# MCU_Do_An_2.net
KiCad netlist of a schematic drawn in Altium Designer
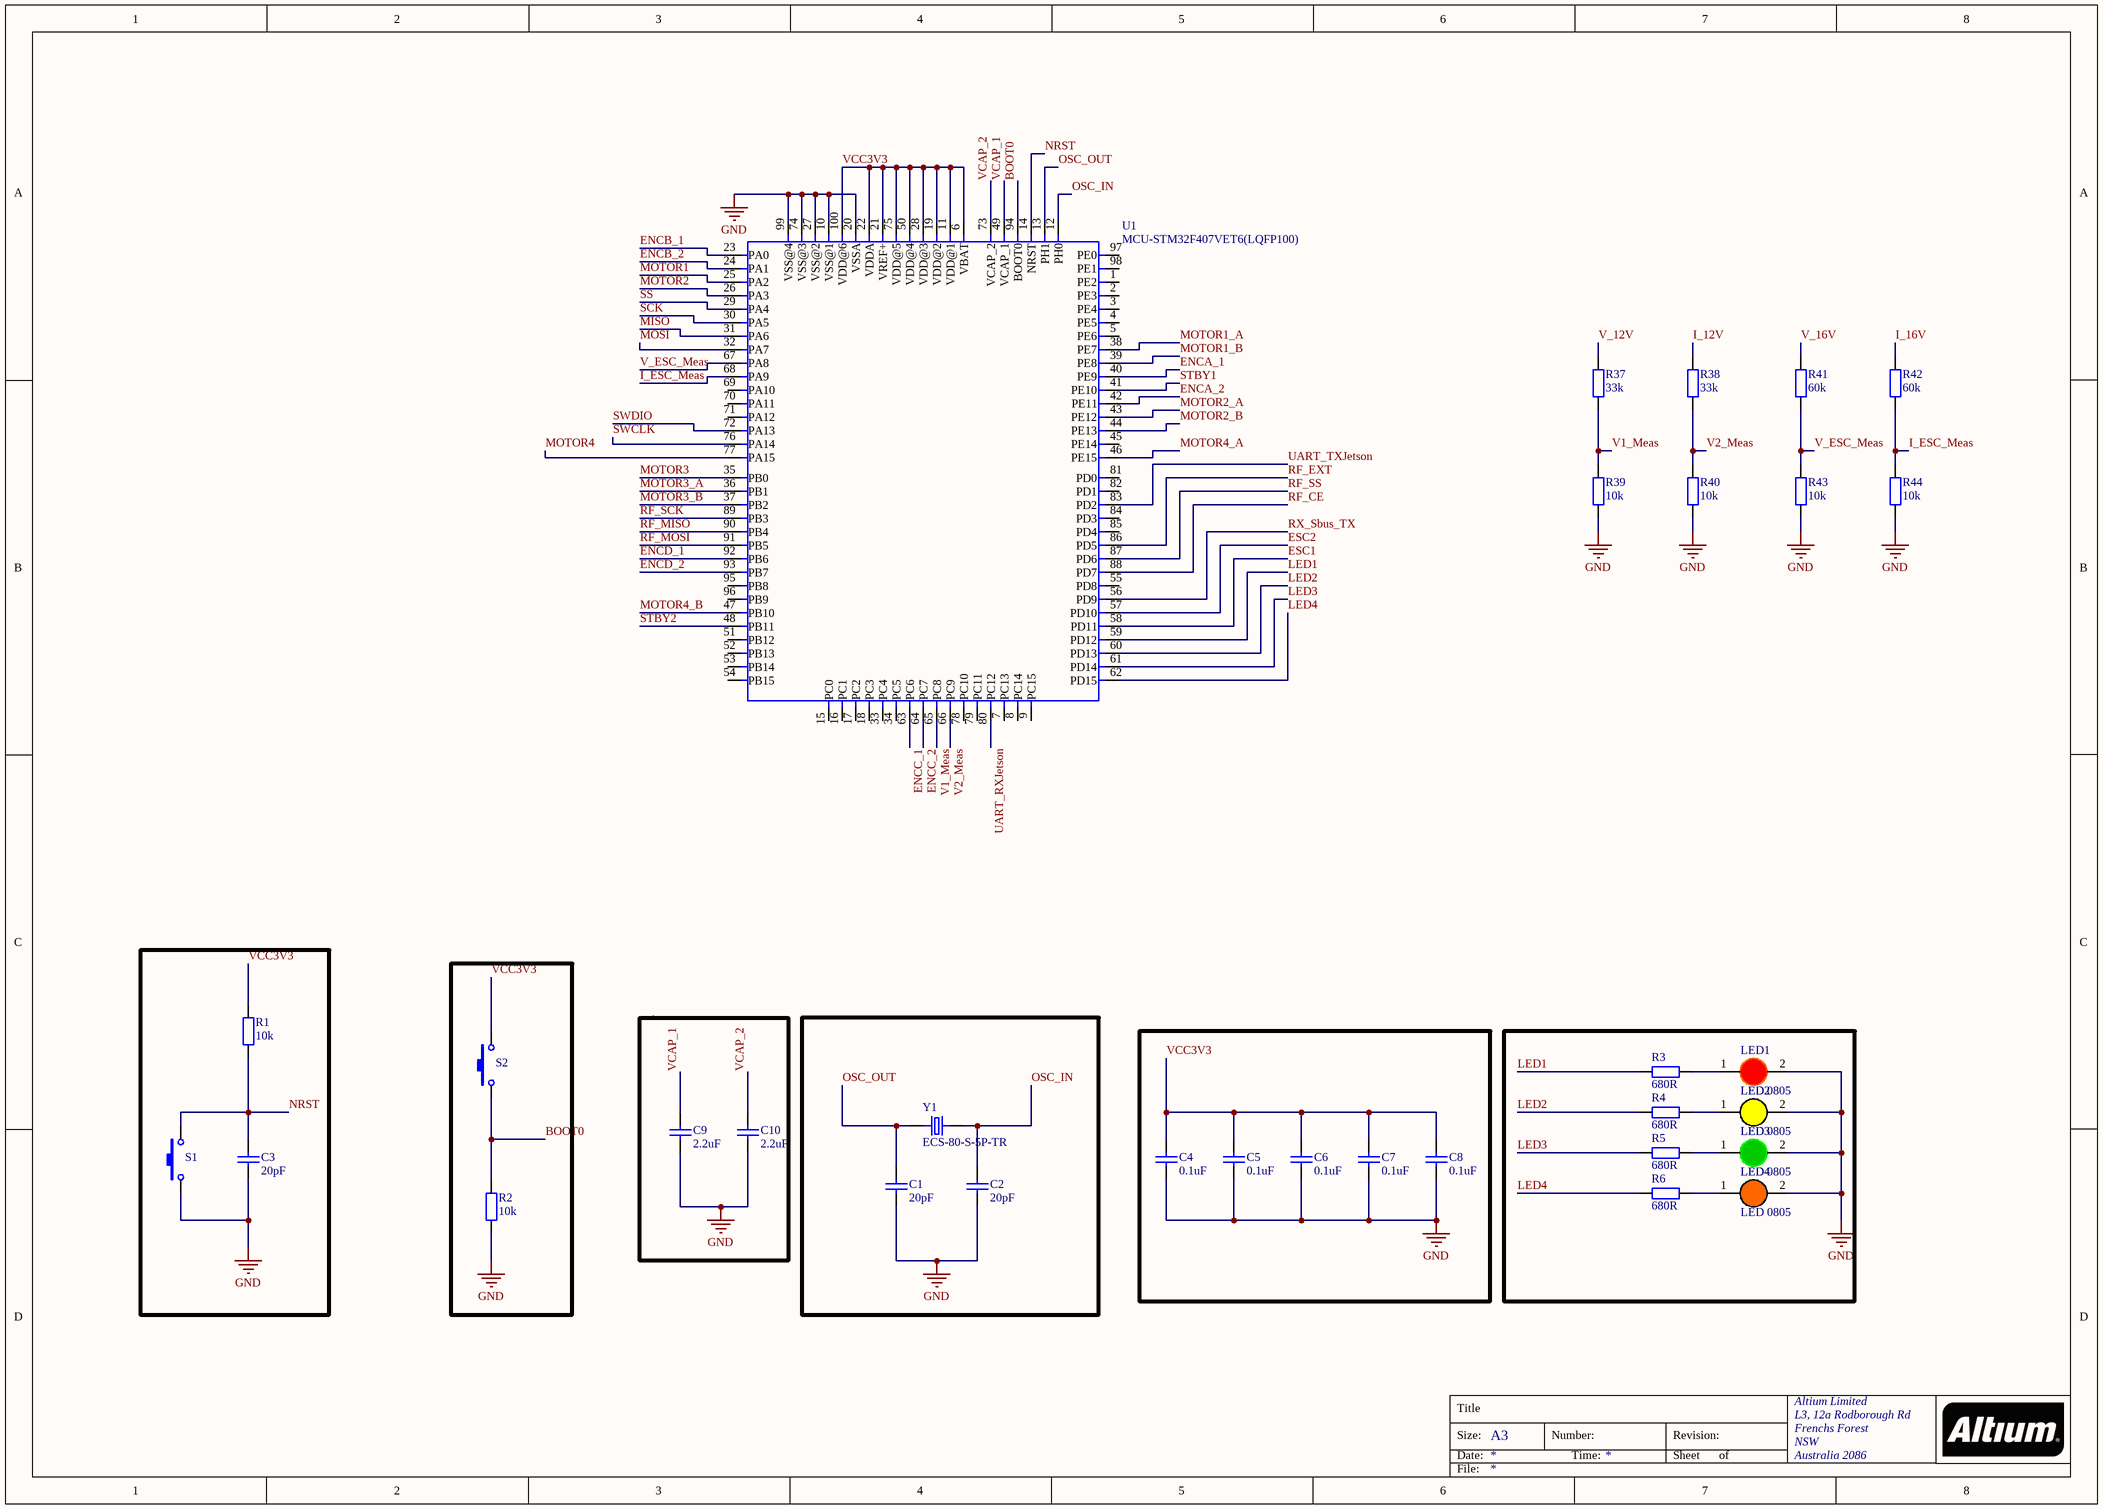
[diagram p0: MCU_Do_An_2.SchDoc]

(export (version "E")
  (design (tool "Eeschema 10.0.6"))
  (components
    (comp (ref "C1")
      (value "20pF")
      (footprint "tu 0805")
      (description "Dán")
      (libsource (lib "Tu dien") (part "Tu 0805 20pF 50V 10%"))
    )
    (comp (ref "C2")
      (value "20pF")
      (footprint "tu 0805")
      (description "Dán")
      (libsource (lib "Tu dien") (part "Tu 0805 20pF 50V 10%"))
    )
    (comp (ref "C3")
      (value "20pF")
      (footprint "tu 0805")
      (description "Dán")
      (libsource (lib "Tu dien") (part "Tu 0805 20pF 50V 10%"))
    )
    (comp (ref "C4")
      (value "0.1uF")
      (footprint "tu 0805")
      (description "Dán")
      (libsource (lib "Tu dien") (part "Tu 0805 20pF 50V 10%"))
    )
    (comp (ref "C5")
      (value "0.1uF")
      (footprint "tu 0805")
      (description "Dán")
      (libsource (lib "Tu dien") (part "Tu 0805 20pF 50V 10%"))
    )
    (comp (ref "C6")
      (value "0.1uF")
      (footprint "tu 0805")
      (description "Dán")
      (libsource (lib "Tu dien") (part "Tu 0805 20pF 50V 10%"))
    )
    (comp (ref "C7")
      (value "0.1uF")
      (footprint "tu 0805")
      (description "Dán")
      (libsource (lib "Tu dien") (part "Tu 0805 20pF 50V 10%"))
    )
    (comp (ref "C8")
      (value "0.1uF")
      (footprint "tu 0805")
      (description "Dán")
      (libsource (lib "Tu dien") (part "Tu 0805 20pF 50V 10%"))
    )
    (comp (ref "C9")
      (value "2.2uF")
      (footprint "tu 0805")
      (description "Dán")
      (libsource (lib "Tu dien") (part "Tu 0805 225 25V 10%"))
    )
    (comp (ref "C10")
      (value "2.2uF")
      (footprint "tu 0805")
      (description "Dán")
      (libsource (lib "Tu dien") (part "Tu 0805 225 25V 10%"))
    )
    (comp (ref "LED1")
      (value "LED 0805")
      (footprint "LED-0805-Red")
      (description "Dán")
      (libsource (lib "Led") (part "LED 0805 Do"))
    )
    (comp (ref "LED2")
      (value "LED 0805")
      (footprint "LED-0805-Yellow")
      (description "Dán")
      (libsource (lib "Led") (part "LED 0805 Vang"))
    )
    (comp (ref "LED3")
      (value "LED 0805")
      (footprint "LED-0805-Green")
      (description "Dán")
      (libsource (lib "Led") (part "LED 0805 Xanh La"))
    )
    (comp (ref "LED4")
      (value "LED 0805")
      (footprint "LED-0805-Orange")
      (description "Dán")
      (libsource (lib "Led") (part "LED 0805 Cam"))
    )
    (comp (ref "R1")
      (value "10k")
      (footprint "tro smd 0603")
      (description "Dán")
      (libsource (lib "Dien Tro") (part "Tro 0603 1% 10k"))
    )
    (comp (ref "R2")
      (value "10k")
      (footprint "tro smd 0603")
      (description "Dán")
      (libsource (lib "Dien Tro") (part "Tro 0603 1% 10k"))
    )
    (comp (ref "R3")
      (value "680R")
      (footprint "tro smd 0603")
      (description "Dán")
      (libsource (lib "Dien Tro") (part "Tro 0603 1% 680R"))
    )
    (comp (ref "R4")
      (value "680R")
      (footprint "tro smd 0603")
      (description "Dán")
      (libsource (lib "Dien Tro") (part "Tro 0603 1% 680R"))
    )
    (comp (ref "R5")
      (value "680R")
      (footprint "tro smd 0603")
      (description "Dán")
      (libsource (lib "Dien Tro") (part "Tro 0603 1% 680R"))
    )
    (comp (ref "R6")
      (value "680R")
      (footprint "tro smd 0603")
      (description "Dán")
      (libsource (lib "Dien Tro") (part "Tro 0603 1% 680R"))
    )
    (comp (ref "R37")
      (value "33k")
      (footprint "Tro smd 0603")
      (description "Dán")
      (libsource (lib "Dien Tro") (part "Tro 0603 1% 33k"))
    )
    (comp (ref "R38")
      (value "33k")
      (footprint "Tro smd 0603")
      (description "Dán")
      (libsource (lib "Dien Tro") (part "Tro 0603 1% 33k"))
    )
    (comp (ref "R39")
      (value "10k")
      (footprint "tro smd 0603")
      (description "Dán")
      (libsource (lib "Dien Tro") (part "Tro 0603 1% 10k"))
    )
    (comp (ref "R40")
      (value "10k")
      (footprint "tro smd 0603")
      (description "Dán")
      (libsource (lib "Dien Tro") (part "Tro 0603 1% 10k"))
    )
    (comp (ref "R41")
      (value "60k")
      (footprint "Tro smd 0603")
      (description "Dán")
      (libsource (lib "Dien Tro") (part "Tro 0603 1% 33k"))
    )
    (comp (ref "R42")
      (value "60k")
      (footprint "Tro smd 0603")
      (description "Dán")
      (libsource (lib "Dien Tro") (part "Tro 0603 1% 33k"))
    )
    (comp (ref "R43")
      (value "10k")
      (footprint "tro smd 0603")
      (description "Dán")
      (libsource (lib "Dien Tro") (part "Tro 0603 1% 10k"))
    )
    (comp (ref "R44")
      (value "10k")
      (footprint "tro smd 0603")
      (description "Dán")
      (libsource (lib "Dien Tro") (part "Tro 0603 1% 10k"))
    )
    (comp (ref "S1")
      (value "SW-SMD")
      (footprint "SW-SMD")
      (description "Switch")
      (fields (field (name "PUBLISHER") "Altium Limited"))
      (libsource (lib "NBBLib 14-03-2012") (part "SW-SMD"))
    )
    (comp (ref "S2")
      (value "SW-SMD")
      (footprint "SW-SMD")
      (description "Switch")
      (fields (field (name "PUBLISHER") "Altium Limited"))
      (libsource (lib "NBBLib 14-03-2012") (part "SW-SMD"))
    )
    (comp (ref "U1")
      (value "MCU-STM32F407VET6(LQFP100)")
      (footprint "LQFP100-0.5-13.8X13.8MM")
      (fields (field (name "MP") "STM32F407VET6") (field (name "MF") "STMicroelectronics"))
      (libsource (lib "MCU-STM32F407VET6_LQFP100_") (part "MCU-STM32F407VET6(LQFP100)"))
    )
    (comp (ref "Y1")
      (value "ECS-80-S-5P-TR")
      (footprint "XTAL_ECS-80-S-5P-TR")
      (description "CRYSTAL SMD")
      (libsource (lib "ECS-80-S-5P-TR") (part "ECS-80-S-5P-TR"))
    )
  )
  (nets
    (net (code "1") (name "/BOOT0") (class "Default")
      (node (ref "R2") (pin "2") (pinfunction "2_2") (pintype "passive"))
      (node (ref "S2") (pin "1") (pinfunction "1_1") (pintype "passive"))
      (node (ref "U1") (pin "94") (pinfunction "BOOT0_94") (pintype "bidirectional"))
    )
    (net (code "2") (name "/ENCA_1") (class "Default")
      (node (ref "U1") (pin "40") (pinfunction "PE9_40") (pintype "bidirectional"))
    )
    (net (code "3") (name "/ENCA_2") (class "Default")
      (node (ref "U1") (pin "42") (pinfunction "PE11_42") (pintype "bidirectional"))
    )
    (net (code "4") (name "/ENCB_1") (class "Default")
      (node (ref "U1") (pin "23") (pinfunction "PA0_23") (pintype "bidirectional"))
    )
    (net (code "5") (name "/ENCB_2") (class "Default")
      (node (ref "U1") (pin "24") (pinfunction "PA1_24") (pintype "bidirectional"))
    )
    (net (code "6") (name "/ENCC_1") (class "Default")
      (node (ref "U1") (pin "63") (pinfunction "PC6_63") (pintype "bidirectional"))
    )
    (net (code "7") (name "/ENCC_2") (class "Default")
      (node (ref "U1") (pin "64") (pinfunction "PC7_64") (pintype "bidirectional"))
    )
    (net (code "8") (name "/ENCD_1") (class "Default")
      (node (ref "U1") (pin "92") (pinfunction "PB6_92") (pintype "bidirectional"))
    )
    (net (code "9") (name "/ENCD_2") (class "Default")
      (node (ref "U1") (pin "93") (pinfunction "PB7_93") (pintype "bidirectional"))
    )
    (net (code "10") (name "/ESC1") (class "Default")
      (node (ref "U1") (pin "58") (pinfunction "PD11_58") (pintype "bidirectional"))
    )
    (net (code "11") (name "/ESC2") (class "Default")
      (node (ref "U1") (pin "57") (pinfunction "PD10_57") (pintype "bidirectional"))
    )
    (net (code "12") (name "/I_12V") (class "Default")
      (node (ref "R38") (pin "2") (pinfunction "2_2") (pintype "passive"))
    )
    (net (code "13") (name "/I_16V") (class "Default")
      (node (ref "R42") (pin "2") (pinfunction "2_2") (pintype "passive"))
    )
    (net (code "14") (name "/I_ESC_Meas") (class "Default")
      (node (ref "R42") (pin "1") (pinfunction "1_1") (pintype "passive"))
      (node (ref "R44") (pin "2") (pinfunction "2_2") (pintype "passive"))
      (node (ref "U1") (pin "68") (pinfunction "PA9_68") (pintype "bidirectional"))
    )
    (net (code "15") (name "/LED1") (class "Default")
      (node (ref "R3") (pin "1") (pinfunction "1_1") (pintype "passive"))
      (node (ref "U1") (pin "59") (pinfunction "PD12_59") (pintype "bidirectional"))
    )
    (net (code "16") (name "/LED2") (class "Default")
      (node (ref "R4") (pin "1") (pinfunction "1_1") (pintype "passive"))
      (node (ref "U1") (pin "60") (pinfunction "PD13_60") (pintype "bidirectional"))
    )
    (net (code "17") (name "/LED3") (class "Default")
      (node (ref "R5") (pin "1") (pinfunction "1_1") (pintype "passive"))
      (node (ref "U1") (pin "61") (pinfunction "PD14_61") (pintype "bidirectional"))
    )
    (net (code "18") (name "/LED4") (class "Default")
      (node (ref "R6") (pin "1") (pinfunction "1_1") (pintype "passive"))
      (node (ref "U1") (pin "62") (pinfunction "PD15_62") (pintype "bidirectional"))
    )
    (net (code "19") (name "/MISO") (class "Default")
      (node (ref "U1") (pin "31") (pinfunction "PA6_31") (pintype "bidirectional"))
    )
    (net (code "20") (name "/MOSI") (class "Default")
      (node (ref "U1") (pin "32") (pinfunction "PA7_32") (pintype "bidirectional"))
    )
    (net (code "21") (name "/MOTOR1") (class "Default")
      (node (ref "U1") (pin "25") (pinfunction "PA2_25") (pintype "bidirectional"))
    )
    (net (code "22") (name "/MOTOR1_A") (class "Default")
      (node (ref "U1") (pin "38") (pinfunction "PE7_38") (pintype "bidirectional"))
    )
    (net (code "23") (name "/MOTOR1_B") (class "Default")
      (node (ref "U1") (pin "39") (pinfunction "PE8_39") (pintype "bidirectional"))
    )
    (net (code "24") (name "/MOTOR2") (class "Default")
      (node (ref "U1") (pin "26") (pinfunction "PA3_26") (pintype "bidirectional"))
    )
    (net (code "25") (name "/MOTOR2_A") (class "Default")
      (node (ref "U1") (pin "43") (pinfunction "PE12_43") (pintype "bidirectional"))
    )
    (net (code "26") (name "/MOTOR2_B") (class "Default")
      (node (ref "U1") (pin "44") (pinfunction "PE13_44") (pintype "bidirectional"))
    )
    (net (code "27") (name "/MOTOR3") (class "Default")
      (node (ref "U1") (pin "35") (pinfunction "PB0_35") (pintype "bidirectional"))
    )
    (net (code "28") (name "/MOTOR3_A") (class "Default")
      (node (ref "U1") (pin "36") (pinfunction "PB1_36") (pintype "bidirectional"))
    )
    (net (code "29") (name "/MOTOR3_B") (class "Default")
      (node (ref "U1") (pin "37") (pinfunction "PB2_37") (pintype "bidirectional"))
    )
    (net (code "30") (name "/MOTOR4") (class "Default")
      (node (ref "U1") (pin "77") (pinfunction "PA15_77") (pintype "bidirectional"))
    )
    (net (code "31") (name "/MOTOR4_A") (class "Default")
      (node (ref "U1") (pin "46") (pinfunction "PE15_46") (pintype "bidirectional"))
    )
    (net (code "32") (name "/MOTOR4_B") (class "Default")
      (node (ref "U1") (pin "47") (pinfunction "PB10_47") (pintype "bidirectional"))
    )
    (net (code "33") (name "/NRST") (class "Default")
      (node (ref "C3") (pin "1") (pinfunction "1_1") (pintype "passive"))
      (node (ref "R1") (pin "1") (pinfunction "1_1") (pintype "passive"))
      (node (ref "S1") (pin "2") (pinfunction "2_2") (pintype "passive"))
      (node (ref "U1") (pin "14") (pinfunction "NRST_14") (pintype "bidirectional"))
    )
    (net (code "34") (name "/OSC_IN") (class "Default")
      (node (ref "C2") (pin "1") (pinfunction "1_1") (pintype "passive"))
      (node (ref "U1") (pin "12") (pinfunction "PH0_12") (pintype "bidirectional"))
      (node (ref "Y1") (pin "2") (pinfunction "2_2") (pintype "passive"))
    )
    (net (code "35") (name "/OSC_OUT") (class "Default")
      (node (ref "C1") (pin "1") (pinfunction "1_1") (pintype "passive"))
      (node (ref "U1") (pin "13") (pinfunction "PH1_13") (pintype "bidirectional"))
      (node (ref "Y1") (pin "1") (pinfunction "1_1") (pintype "passive"))
    )
    (net (code "36") (name "/RF_CE") (class "Default")
      (node (ref "U1") (pin "88") (pinfunction "PD7_88") (pintype "bidirectional"))
    )
    (net (code "37") (name "/RF_EXT") (class "Default")
      (node (ref "U1") (pin "86") (pinfunction "PD5_86") (pintype "bidirectional"))
    )
    (net (code "38") (name "/RF_MISO") (class "Default")
      (node (ref "U1") (pin "90") (pinfunction "PB4_90") (pintype "bidirectional"))
    )
    (net (code "39") (name "/RF_MOSI") (class "Default")
      (node (ref "U1") (pin "91") (pinfunction "PB5_91") (pintype "bidirectional"))
    )
    (net (code "40") (name "/RF_SCK") (class "Default")
      (node (ref "U1") (pin "89") (pinfunction "PB3_89") (pintype "bidirectional"))
    )
    (net (code "41") (name "/RF_SS") (class "Default")
      (node (ref "U1") (pin "87") (pinfunction "PD6_87") (pintype "bidirectional"))
    )
    (net (code "42") (name "/RX_Sbus_TX") (class "Default")
      (node (ref "U1") (pin "56") (pinfunction "PD9_56") (pintype "bidirectional"))
    )
    (net (code "43") (name "/SCK") (class "Default")
      (node (ref "U1") (pin "30") (pinfunction "PA5_30") (pintype "bidirectional"))
    )
    (net (code "44") (name "/SS") (class "Default")
      (node (ref "U1") (pin "29") (pinfunction "PA4_29") (pintype "bidirectional"))
    )
    (net (code "45") (name "/STBY1") (class "Default")
      (node (ref "U1") (pin "41") (pinfunction "PE10_41") (pintype "bidirectional"))
    )
    (net (code "46") (name "/STBY2") (class "Default")
      (node (ref "U1") (pin "48") (pinfunction "PB11_48") (pintype "bidirectional"))
    )
    (net (code "47") (name "/SWCLK") (class "Default")
      (node (ref "U1") (pin "76") (pinfunction "PA14_76") (pintype "bidirectional"))
    )
    (net (code "48") (name "/SWDIO") (class "Default")
      (node (ref "U1") (pin "72") (pinfunction "PA13_72") (pintype "bidirectional"))
    )
    (net (code "49") (name "/UART_RXJetson") (class "Default")
      (node (ref "U1") (pin "80") (pinfunction "PC12_80") (pintype "bidirectional"))
    )
    (net (code "50") (name "/UART_TXJetson") (class "Default")
      (node (ref "U1") (pin "83") (pinfunction "PD2_83") (pintype "bidirectional"))
    )
    (net (code "51") (name "/V1_Meas") (class "Default")
      (node (ref "R37") (pin "1") (pinfunction "1_1") (pintype "passive"))
      (node (ref "R39") (pin "2") (pinfunction "2_2") (pintype "passive"))
      (node (ref "U1") (pin "65") (pinfunction "PC8_65") (pintype "bidirectional"))
    )
    (net (code "52") (name "/V2_Meas") (class "Default")
      (node (ref "R38") (pin "1") (pinfunction "1_1") (pintype "passive"))
      (node (ref "R40") (pin "2") (pinfunction "2_2") (pintype "passive"))
      (node (ref "U1") (pin "66") (pinfunction "PC9_66") (pintype "bidirectional"))
    )
    (net (code "53") (name "/VCAP_1") (class "Default")
      (node (ref "C9") (pin "2") (pinfunction "2_2") (pintype "passive"))
      (node (ref "U1") (pin "49") (pinfunction "VCAP_1_49") (pintype "bidirectional"))
    )
    (net (code "54") (name "/VCAP_2") (class "Default")
      (node (ref "C10") (pin "2") (pinfunction "2_2") (pintype "passive"))
      (node (ref "U1") (pin "73") (pinfunction "VCAP_2_73") (pintype "bidirectional"))
    )
    (net (code "55") (name "/VCC3V3") (class "Default")
      (node (ref "C4") (pin "1") (pinfunction "1_1") (pintype "passive"))
      (node (ref "C5") (pin "1") (pinfunction "1_1") (pintype "passive"))
      (node (ref "C6") (pin "1") (pinfunction "1_1") (pintype "passive"))
      (node (ref "C7") (pin "1") (pinfunction "1_1") (pintype "passive"))
      (node (ref "C8") (pin "1") (pinfunction "1_1") (pintype "passive"))
      (node (ref "R1") (pin "2") (pinfunction "2_2") (pintype "passive"))
      (node (ref "S2") (pin "2") (pinfunction "2_2") (pintype "passive"))
      (node (ref "U1") (pin "100") (pinfunction "VDD@6_100") (pintype "bidirectional"))
      (node (ref "U1") (pin "11") (pinfunction "VDD@1_11") (pintype "bidirectional"))
      (node (ref "U1") (pin "19") (pinfunction "VDD@2_19") (pintype "bidirectional"))
      (node (ref "U1") (pin "21") (pinfunction "VREF+_21") (pintype "bidirectional"))
      (node (ref "U1") (pin "22") (pinfunction "VDDA_22") (pintype "bidirectional"))
      (node (ref "U1") (pin "28") (pinfunction "VDD@3_28") (pintype "bidirectional"))
      (node (ref "U1") (pin "50") (pinfunction "VDD@4_50") (pintype "bidirectional"))
      (node (ref "U1") (pin "6") (pinfunction "VBAT_6") (pintype "bidirectional"))
      (node (ref "U1") (pin "75") (pinfunction "VDD@5_75") (pintype "bidirectional"))
    )
    (net (code "56") (name "/V_12V") (class "Default")
      (node (ref "R37") (pin "2") (pinfunction "2_2") (pintype "passive"))
    )
    (net (code "57") (name "/V_16V") (class "Default")
      (node (ref "R41") (pin "2") (pinfunction "2_2") (pintype "passive"))
    )
    (net (code "58") (name "/V_ESC_Meas") (class "Default")
      (node (ref "R41") (pin "1") (pinfunction "1_1") (pintype "passive"))
      (node (ref "R43") (pin "2") (pinfunction "2_2") (pintype "passive"))
      (node (ref "U1") (pin "67") (pinfunction "PA8_67") (pintype "bidirectional"))
    )
    (net (code "59") (name "GND") (class "Default")
      (node (ref "C1") (pin "2") (pinfunction "2_2") (pintype "passive"))
      (node (ref "C10") (pin "1") (pinfunction "1_1") (pintype "passive"))
      (node (ref "C2") (pin "2") (pinfunction "2_2") (pintype "passive"))
      (node (ref "C3") (pin "2") (pinfunction "2_2") (pintype "passive"))
      (node (ref "C4") (pin "2") (pinfunction "2_2") (pintype "passive"))
      (node (ref "C5") (pin "2") (pinfunction "2_2") (pintype "passive"))
      (node (ref "C6") (pin "2") (pinfunction "2_2") (pintype "passive"))
      (node (ref "C7") (pin "2") (pinfunction "2_2") (pintype "passive"))
      (node (ref "C8") (pin "2") (pinfunction "2_2") (pintype "passive"))
      (node (ref "C9") (pin "1") (pinfunction "1_1") (pintype "passive"))
      (node (ref "LED1") (pin "2") (pinfunction "K_2") (pintype "passive"))
      (node (ref "LED2") (pin "2") (pinfunction "K_2") (pintype "passive"))
      (node (ref "LED3") (pin "2") (pinfunction "K_2") (pintype "passive"))
      (node (ref "LED4") (pin "2") (pinfunction "K_2") (pintype "passive"))
      (node (ref "R2") (pin "1") (pinfunction "1_1") (pintype "passive"))
      (node (ref "R39") (pin "1") (pinfunction "1_1") (pintype "passive"))
      (node (ref "R40") (pin "1") (pinfunction "1_1") (pintype "passive"))
      (node (ref "R43") (pin "1") (pinfunction "1_1") (pintype "passive"))
      (node (ref "R44") (pin "1") (pinfunction "1_1") (pintype "passive"))
      (node (ref "S1") (pin "1") (pinfunction "1_1") (pintype "passive"))
      (node (ref "U1") (pin "10") (pinfunction "VSS@1_10") (pintype "bidirectional"))
      (node (ref "U1") (pin "20") (pinfunction "VSSA_20") (pintype "bidirectional"))
      (node (ref "U1") (pin "27") (pinfunction "VSS@2_27") (pintype "bidirectional"))
      (node (ref "U1") (pin "74") (pinfunction "VSS@3_74") (pintype "bidirectional"))
      (node (ref "U1") (pin "99") (pinfunction "VSS@4_99") (pintype "bidirectional"))
    )
    (net (code "60") (name "Net-(LED1-A)") (class "Default")
      (node (ref "LED1") (pin "1") (pinfunction "A_1") (pintype "passive"))
      (node (ref "R3") (pin "2") (pinfunction "2_2") (pintype "passive"))
    )
    (net (code "61") (name "Net-(LED2-A)") (class "Default")
      (node (ref "LED2") (pin "1") (pinfunction "A_1") (pintype "passive"))
      (node (ref "R4") (pin "2") (pinfunction "2_2") (pintype "passive"))
    )
    (net (code "62") (name "Net-(LED3-A)") (class "Default")
      (node (ref "LED3") (pin "1") (pinfunction "A_1") (pintype "passive"))
      (node (ref "R5") (pin "2") (pinfunction "2_2") (pintype "passive"))
    )
    (net (code "63") (name "Net-(LED4-A)") (class "Default")
      (node (ref "LED4") (pin "1") (pinfunction "A_1") (pintype "passive"))
      (node (ref "R6") (pin "2") (pinfunction "2_2") (pintype "passive"))
    )
    (net (code "64") (name "unconnected-(U1-PA10-Pad69)") (class "Default")
      (node (ref "U1") (pin "69") (pinfunction "PA10_69") (pintype "bidirectional"))
    )
    (net (code "65") (name "unconnected-(U1-PA11-Pad70)") (class "Default")
      (node (ref "U1") (pin "70") (pinfunction "PA11_70") (pintype "bidirectional"))
    )
    (net (code "66") (name "unconnected-(U1-PA12-Pad71)") (class "Default")
      (node (ref "U1") (pin "71") (pinfunction "PA12_71") (pintype "bidirectional"))
    )
    (net (code "67") (name "unconnected-(U1-PB8-Pad95)") (class "Default")
      (node (ref "U1") (pin "95") (pinfunction "PB8_95") (pintype "bidirectional"))
    )
    (net (code "68") (name "unconnected-(U1-PB9-Pad96)") (class "Default")
      (node (ref "U1") (pin "96") (pinfunction "PB9_96") (pintype "bidirectional"))
    )
    (net (code "69") (name "unconnected-(U1-PB12-Pad51)") (class "Default")
      (node (ref "U1") (pin "51") (pinfunction "PB12_51") (pintype "bidirectional"))
    )
    (net (code "70") (name "unconnected-(U1-PB13-Pad52)") (class "Default")
      (node (ref "U1") (pin "52") (pinfunction "PB13_52") (pintype "bidirectional"))
    )
    (net (code "71") (name "unconnected-(U1-PB14-Pad53)") (class "Default")
      (node (ref "U1") (pin "53") (pinfunction "PB14_53") (pintype "bidirectional"))
    )
    (net (code "72") (name "unconnected-(U1-PB15-Pad54)") (class "Default")
      (node (ref "U1") (pin "54") (pinfunction "PB15_54") (pintype "bidirectional"))
    )
    (net (code "73") (name "unconnected-(U1-PC0-Pad15)") (class "Default")
      (node (ref "U1") (pin "15") (pinfunction "PC0_15") (pintype "bidirectional"))
    )
    (net (code "74") (name "unconnected-(U1-PC1-Pad16)") (class "Default")
      (node (ref "U1") (pin "16") (pinfunction "PC1_16") (pintype "bidirectional"))
    )
    (net (code "75") (name "unconnected-(U1-PC2-Pad17)") (class "Default")
      (node (ref "U1") (pin "17") (pinfunction "PC2_17") (pintype "bidirectional"))
    )
    (net (code "76") (name "unconnected-(U1-PC3-Pad18)") (class "Default")
      (node (ref "U1") (pin "18") (pinfunction "PC3_18") (pintype "bidirectional"))
    )
    (net (code "77") (name "unconnected-(U1-PC4-Pad33)") (class "Default")
      (node (ref "U1") (pin "33") (pinfunction "PC4_33") (pintype "bidirectional"))
    )
    (net (code "78") (name "unconnected-(U1-PC5-Pad34)") (class "Default")
      (node (ref "U1") (pin "34") (pinfunction "PC5_34") (pintype "bidirectional"))
    )
    (net (code "79") (name "unconnected-(U1-PC10-Pad78)") (class "Default")
      (node (ref "U1") (pin "78") (pinfunction "PC10_78") (pintype "bidirectional"))
    )
    (net (code "80") (name "unconnected-(U1-PC11-Pad79)") (class "Default")
      (node (ref "U1") (pin "79") (pinfunction "PC11_79") (pintype "bidirectional"))
    )
    (net (code "81") (name "unconnected-(U1-PC13-Pad7)") (class "Default")
      (node (ref "U1") (pin "7") (pinfunction "PC13_7") (pintype "bidirectional"))
    )
    (net (code "82") (name "unconnected-(U1-PC14-Pad8)") (class "Default")
      (node (ref "U1") (pin "8") (pinfunction "PC14_8") (pintype "bidirectional"))
    )
    (net (code "83") (name "unconnected-(U1-PC15-Pad9)") (class "Default")
      (node (ref "U1") (pin "9") (pinfunction "PC15_9") (pintype "bidirectional"))
    )
    (net (code "84") (name "unconnected-(U1-PD0-Pad81)") (class "Default")
      (node (ref "U1") (pin "81") (pinfunction "PD0_81") (pintype "bidirectional"))
    )
    (net (code "85") (name "unconnected-(U1-PD1-Pad82)") (class "Default")
      (node (ref "U1") (pin "82") (pinfunction "PD1_82") (pintype "bidirectional"))
    )
    (net (code "86") (name "unconnected-(U1-PD3-Pad84)") (class "Default")
      (node (ref "U1") (pin "84") (pinfunction "PD3_84") (pintype "bidirectional"))
    )
    (net (code "87") (name "unconnected-(U1-PD4-Pad85)") (class "Default")
      (node (ref "U1") (pin "85") (pinfunction "PD4_85") (pintype "bidirectional"))
    )
    (net (code "88") (name "unconnected-(U1-PD8-Pad55)") (class "Default")
      (node (ref "U1") (pin "55") (pinfunction "PD8_55") (pintype "bidirectional"))
    )
    (net (code "89") (name "unconnected-(U1-PE0-Pad97)") (class "Default")
      (node (ref "U1") (pin "97") (pinfunction "PE0_97") (pintype "bidirectional"))
    )
    (net (code "90") (name "unconnected-(U1-PE1-Pad98)") (class "Default")
      (node (ref "U1") (pin "98") (pinfunction "PE1_98") (pintype "bidirectional"))
    )
    (net (code "91") (name "unconnected-(U1-PE2-Pad1)") (class "Default")
      (node (ref "U1") (pin "1") (pinfunction "PE2_1") (pintype "bidirectional"))
    )
    (net (code "92") (name "unconnected-(U1-PE3-Pad2)") (class "Default")
      (node (ref "U1") (pin "2") (pinfunction "PE3_2") (pintype "bidirectional"))
    )
    (net (code "93") (name "unconnected-(U1-PE4-Pad3)") (class "Default")
      (node (ref "U1") (pin "3") (pinfunction "PE4_3") (pintype "bidirectional"))
    )
    (net (code "94") (name "unconnected-(U1-PE5-Pad4)") (class "Default")
      (node (ref "U1") (pin "4") (pinfunction "PE5_4") (pintype "bidirectional"))
    )
    (net (code "95") (name "unconnected-(U1-PE6-Pad5)") (class "Default")
      (node (ref "U1") (pin "5") (pinfunction "PE6_5") (pintype "bidirectional"))
    )
    (net (code "96") (name "unconnected-(U1-PE14-Pad45)") (class "Default")
      (node (ref "U1") (pin "45") (pinfunction "PE14_45") (pintype "bidirectional"))
    )
  )
)
